# Sheet1.net
KiCad netlist of a schematic drawn in Altium Designer
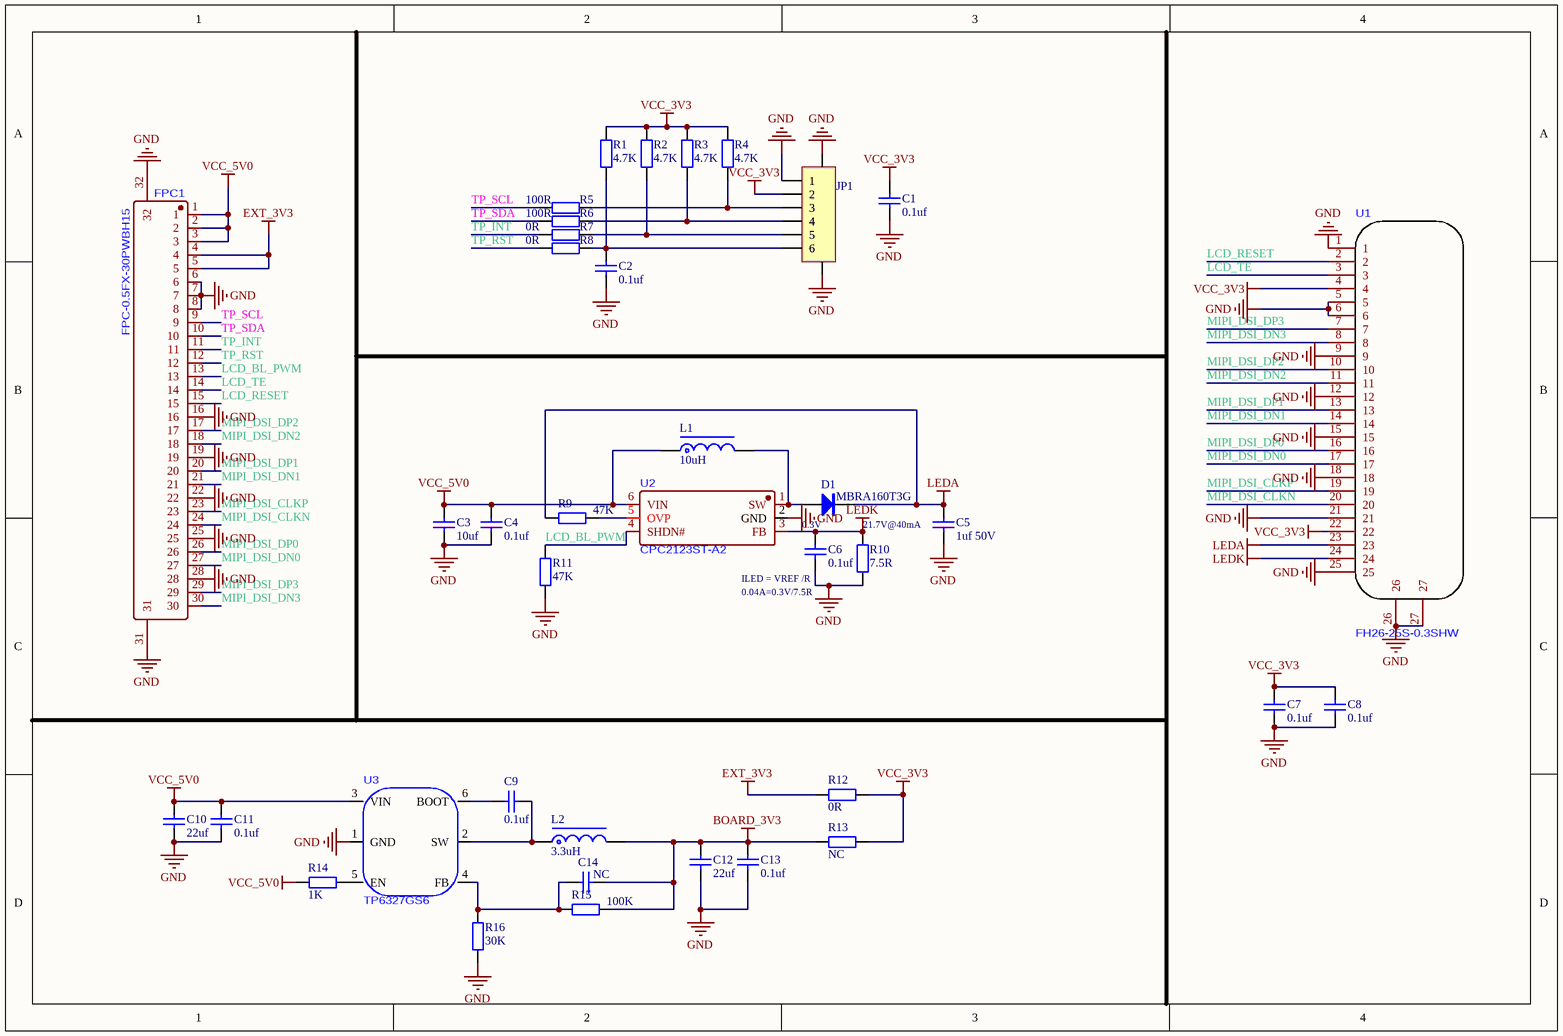
[diagram p0: Sheet1.SchDoc]

(export (version "E")
  (design (tool "Eeschema 10.0.6"))
  (components
    (comp (ref "C1")
      (value "0.1uf")
      (footprint "PCB1:C0402_L")
      (description "贴片电容/MLCC电容")
      (libsource (lib "5.5_MIPI_LCD") (part "C"))
    )
    (comp (ref "C2")
      (value "0.1uf")
      (footprint "PCB1:C0402_L")
      (description "贴片电容/MLCC电容")
      (libsource (lib "5.5_MIPI_LCD") (part "C"))
    )
    (comp (ref "C3")
      (value "10uf")
      (footprint "PCB1:C0402_L")
      (description "贴片电容/MLCC电容")
      (libsource (lib "5.5_MIPI_LCD") (part "C"))
    )
    (comp (ref "C4")
      (value "0.1uf")
      (footprint "PCB1:C0402_L")
      (description "贴片电容/MLCC电容")
      (libsource (lib "5.5_MIPI_LCD") (part "C"))
    )
    (comp (ref "C5")
      (value "1uf 50V")
      (footprint "PCB1:C0603_L")
      (description "贴片电容/MLCC电容")
      (libsource (lib "5.5_MIPI_LCD") (part "C"))
    )
    (comp (ref "C6")
      (value "0.1uf")
      (footprint "PCB1:C0402_L")
      (description "贴片电容/MLCC电容")
      (libsource (lib "5.5_MIPI_LCD") (part "C"))
    )
    (comp (ref "C7")
      (value "0.1uf")
      (footprint "PCB1:C0402_L")
      (description "贴片电容/MLCC电容")
      (libsource (lib "5.5_MIPI_LCD") (part "C"))
    )
    (comp (ref "C8")
      (value "0.1uf")
      (footprint "PCB1:C0402_L")
      (description "贴片电容/MLCC电容")
      (libsource (lib "5.5_MIPI_LCD") (part "C"))
    )
    (comp (ref "C9")
      (value "0.1uf")
      (footprint "PCB1:C0402_L")
      (description "贴片电容/MLCC电容")
      (libsource (lib "5.5_MIPI_LCD") (part "C"))
    )
    (comp (ref "C10")
      (value "22uf")
      (footprint "PCB1:C0603_L")
      (description "贴片电容/MLCC电容")
      (libsource (lib "5.5_MIPI_LCD") (part "C"))
    )
    (comp (ref "C11")
      (value "0.1uf")
      (footprint "PCB1:C0402_L")
      (description "贴片电容/MLCC电容")
      (libsource (lib "5.5_MIPI_LCD") (part "C"))
    )
    (comp (ref "C12")
      (value "22uf")
      (footprint "PCB1:C0603_L")
      (description "贴片电容/MLCC电容")
      (libsource (lib "5.5_MIPI_LCD") (part "C"))
    )
    (comp (ref "C13")
      (value "0.1uf")
      (footprint "PCB1:C0402_L")
      (description "贴片电容/MLCC电容")
      (libsource (lib "5.5_MIPI_LCD") (part "C"))
    )
    (comp (ref "C14")
      (value "NC")
      (footprint "PCB1:C0402_L")
      (description "贴片电容/MLCC电容")
      (libsource (lib "5.5_MIPI_LCD") (part "C"))
    )
    (comp (ref "D1")
      (value "MBRA160T3G")
      (footprint "PCB1:SMA")
      (description "整流二极管")
      (libsource (lib "5.5_MIPI_LCD") (part "M7"))
    )
    (comp (ref "FPC1")
      (value "FPC-0.5FX-30PWBH15")
      (footprint "PCB1:FPC-SMD_30P-P0.50_FPC-0.5FX-30PWBH15")
      (libsource (lib "5.5_MIPI_LCD") (part "FPC-0.5FX-30PWBH15"))
    )
    (comp (ref "JP1")
      (value "CON-6P")
      (footprint "PCB1:FPC0.5-WT-6P")
      (description "6P连接器")
      (libsource (lib "5.5_MIPI_LCD") (part "Header 6"))
    )
    (comp (ref "L1")
      (value "10uH")
      (footprint "PCB1:L-SMD-0420")
      (description "一体成型电感")
      (libsource (lib "5.5_MIPI_LCD") (part "L-Molding Choke"))
    )
    (comp (ref "L2")
      (value "3.3uH")
      (footprint "PCB1:L-SMD-0420")
      (description "一体成型电感")
      (libsource (lib "5.5_MIPI_LCD") (part "L-Molding Choke"))
    )
    (comp (ref "R1")
      (value "4.7K")
      (footprint "PCB1:R0402_L")
      (description "贴片电阻")
      (libsource (lib "5.5_MIPI_LCD") (part "R"))
    )
    (comp (ref "R2")
      (value "4.7K")
      (footprint "PCB1:R0402_L")
      (description "贴片电阻")
      (libsource (lib "5.5_MIPI_LCD") (part "R"))
    )
    (comp (ref "R3")
      (value "4.7K")
      (footprint "PCB1:R0402_L")
      (description "贴片电阻")
      (libsource (lib "5.5_MIPI_LCD") (part "R"))
    )
    (comp (ref "R4")
      (value "4.7K")
      (footprint "PCB1:R0402_L")
      (description "贴片电阻")
      (libsource (lib "5.5_MIPI_LCD") (part "R"))
    )
    (comp (ref "R5")
      (value "100R")
      (footprint "PCB1:R0402_L")
      (description "贴片电阻")
      (libsource (lib "5.5_MIPI_LCD") (part "R"))
    )
    (comp (ref "R6")
      (value "100R")
      (footprint "PCB1:R0402_L")
      (description "贴片电阻")
      (libsource (lib "5.5_MIPI_LCD") (part "R"))
    )
    (comp (ref "R7")
      (value "0R")
      (footprint "PCB1:R0402_L")
      (description "贴片电阻")
      (libsource (lib "5.5_MIPI_LCD") (part "R"))
    )
    (comp (ref "R8")
      (value "0R")
      (footprint "PCB1:R0402_L")
      (description "贴片电阻")
      (libsource (lib "5.5_MIPI_LCD") (part "R"))
    )
    (comp (ref "R9")
      (value "47K")
      (footprint "PCB1:R0402_L")
      (description "贴片电阻")
      (libsource (lib "5.5_MIPI_LCD") (part "R"))
    )
    (comp (ref "R10")
      (value "7.5R")
      (footprint "PCB1:R0603_L")
      (description "贴片电阻")
      (libsource (lib "5.5_MIPI_LCD") (part "R"))
    )
    (comp (ref "R11")
      (value "47K")
      (footprint "PCB1:R0402_L")
      (description "贴片电阻")
      (libsource (lib "5.5_MIPI_LCD") (part "R"))
    )
    (comp (ref "R12")
      (value "0R")
      (footprint "PCB1:R0603_L")
      (description "贴片电阻")
      (libsource (lib "5.5_MIPI_LCD") (part "R"))
    )
    (comp (ref "R13")
      (value "NC")
      (footprint "PCB1:R0603_L")
      (description "贴片电阻")
      (libsource (lib "5.5_MIPI_LCD") (part "R"))
    )
    (comp (ref "R14")
      (value "1K")
      (footprint "PCB1:R0402_L")
      (description "贴片电阻")
      (libsource (lib "5.5_MIPI_LCD") (part "R"))
    )
    (comp (ref "R15")
      (value "100K")
      (footprint "PCB1:R0402_L")
      (description "贴片电阻")
      (libsource (lib "5.5_MIPI_LCD") (part "R"))
    )
    (comp (ref "R16")
      (value "30K")
      (footprint "PCB1:R0402_L")
      (description "贴片电阻")
      (libsource (lib "5.5_MIPI_LCD") (part "R"))
    )
    (comp (ref "U1")
      (value "FH26-25S-0.3SHW")
      (footprint "PCB1:CONN-25PIN-FH26-25S-0.3SHW")
      (libsource (lib "5.5_MIPI_LCD") (part "FH26-25S-0.3SHW"))
    )
    (comp (ref "U2")
      (value "CPC2123ST-A2")
      (footprint "PCB1:SOT-23-6_L2.9-W1.6-P0.95-LS2.8-BR")
      (libsource (lib "5.5_MIPI_LCD") (part "CPC2123ST-A2"))
    )
    (comp (ref "U3")
      (value "TP6327GS6")
      (footprint "PCB1:SOT23_6")
      (libsource (lib "5.5_MIPI_LCD") (part "TP6327GS6"))
    )
  )
  (nets
    (net (code "1") (name "/LCD_BL_PWM") (class "Default")
      (node (ref "FPC1") (pin "13") (pinfunction "13_13") (pintype "passive"))
      (node (ref "R11") (pin "2") (pinfunction "2_2") (pintype "passive"))
      (node (ref "U2") (pin "4") (pinfunction "SHDN#_4") (pintype "passive"))
    )
    (net (code "2") (name "/LCD_RESET") (class "Default")
      (node (ref "FPC1") (pin "15") (pinfunction "15_15") (pintype "passive"))
      (node (ref "U1") (pin "2") (pinfunction "2_2") (pintype "passive"))
    )
    (net (code "3") (name "/LCD_TE") (class "Default")
      (node (ref "FPC1") (pin "14") (pinfunction "14_14") (pintype "passive"))
      (node (ref "U1") (pin "3") (pinfunction "3_3") (pintype "passive"))
    )
    (net (code "4") (name "/MIPI_DSI_CLKN") (class "Default")
      (node (ref "FPC1") (pin "24") (pinfunction "24_24") (pintype "passive"))
      (node (ref "U1") (pin "20") (pinfunction "20_20") (pintype "passive"))
    )
    (net (code "5") (name "/MIPI_DSI_CLKP") (class "Default")
      (node (ref "FPC1") (pin "23") (pinfunction "23_23") (pintype "passive"))
      (node (ref "U1") (pin "19") (pinfunction "19_19") (pintype "passive"))
    )
    (net (code "6") (name "/MIPI_DSI_DN0") (class "Default")
      (node (ref "FPC1") (pin "27") (pinfunction "27_27") (pintype "passive"))
      (node (ref "U1") (pin "17") (pinfunction "17_17") (pintype "passive"))
    )
    (net (code "7") (name "/MIPI_DSI_DN1") (class "Default")
      (node (ref "FPC1") (pin "21") (pinfunction "21_21") (pintype "passive"))
      (node (ref "U1") (pin "14") (pinfunction "14_14") (pintype "passive"))
    )
    (net (code "8") (name "/MIPI_DSI_DN2") (class "Default")
      (node (ref "FPC1") (pin "18") (pinfunction "18_18") (pintype "passive"))
      (node (ref "U1") (pin "11") (pinfunction "11_11") (pintype "passive"))
    )
    (net (code "9") (name "/MIPI_DSI_DN3") (class "Default")
      (node (ref "FPC1") (pin "30") (pinfunction "30_30") (pintype "passive"))
      (node (ref "U1") (pin "8") (pinfunction "8_8") (pintype "passive"))
    )
    (net (code "10") (name "/MIPI_DSI_DP0") (class "Default")
      (node (ref "FPC1") (pin "26") (pinfunction "26_26") (pintype "passive"))
      (node (ref "U1") (pin "16") (pinfunction "16_16") (pintype "passive"))
    )
    (net (code "11") (name "/MIPI_DSI_DP1") (class "Default")
      (node (ref "FPC1") (pin "20") (pinfunction "20_20") (pintype "passive"))
      (node (ref "U1") (pin "13") (pinfunction "13_13") (pintype "passive"))
    )
    (net (code "12") (name "/MIPI_DSI_DP2") (class "Default")
      (node (ref "FPC1") (pin "17") (pinfunction "17_17") (pintype "passive"))
      (node (ref "U1") (pin "10") (pinfunction "10_10") (pintype "passive"))
    )
    (net (code "13") (name "/MIPI_DSI_DP3") (class "Default")
      (node (ref "FPC1") (pin "29") (pinfunction "29_29") (pintype "passive"))
      (node (ref "U1") (pin "7") (pinfunction "7_7") (pintype "passive"))
    )
    (net (code "14") (name "/TP_INT") (class "Default")
      (node (ref "FPC1") (pin "11") (pinfunction "11_11") (pintype "passive"))
      (node (ref "R7") (pin "1") (pinfunction "1_1") (pintype "passive"))
    )
    (net (code "15") (name "/TP_RST") (class "Default")
      (node (ref "FPC1") (pin "12") (pinfunction "12_12") (pintype "passive"))
      (node (ref "R8") (pin "1") (pinfunction "1_1") (pintype "passive"))
    )
    (net (code "16") (name "/TP_SCL") (class "Default")
      (node (ref "FPC1") (pin "9") (pinfunction "9_9") (pintype "passive"))
      (node (ref "R5") (pin "1") (pinfunction "1_1") (pintype "passive"))
    )
    (net (code "17") (name "/TP_SDA") (class "Default")
      (node (ref "FPC1") (pin "10") (pinfunction "10_10") (pintype "passive"))
      (node (ref "R6") (pin "1") (pinfunction "1_1") (pintype "passive"))
    )
    (net (code "18") (name "BOARD_3V3") (class "Default")
      (node (ref "C12") (pin "2") (pinfunction "2_2") (pintype "passive"))
      (node (ref "C13") (pin "2") (pinfunction "2_2") (pintype "passive"))
      (node (ref "C14") (pin "1") (pinfunction "1_1") (pintype "passive"))
      (node (ref "L2") (pin "2") (pinfunction "2_2") (pintype "passive"))
      (node (ref "R13") (pin "1") (pinfunction "1_1") (pintype "passive"))
      (node (ref "R15") (pin "1") (pinfunction "1_1") (pintype "passive"))
    )
    (net (code "19") (name "EXT_3V3") (class "Default")
      (node (ref "FPC1") (pin "4") (pinfunction "4_4") (pintype "passive"))
      (node (ref "FPC1") (pin "5") (pinfunction "5_5") (pintype "passive"))
      (node (ref "R12") (pin "1") (pinfunction "1_1") (pintype "passive"))
    )
    (net (code "20") (name "GND") (class "Default")
      (node (ref "C1") (pin "1") (pinfunction "1_1") (pintype "passive"))
      (node (ref "C10") (pin "1") (pinfunction "1_1") (pintype "passive"))
      (node (ref "C11") (pin "1") (pinfunction "1_1") (pintype "passive"))
      (node (ref "C12") (pin "1") (pinfunction "1_1") (pintype "passive"))
      (node (ref "C13") (pin "1") (pinfunction "1_1") (pintype "passive"))
      (node (ref "C2") (pin "1") (pinfunction "1_1") (pintype "passive"))
      (node (ref "C3") (pin "1") (pinfunction "1_1") (pintype "passive"))
      (node (ref "C4") (pin "1") (pinfunction "1_1") (pintype "passive"))
      (node (ref "C5") (pin "1") (pinfunction "1_1") (pintype "passive"))
      (node (ref "C6") (pin "1") (pinfunction "1_1") (pintype "passive"))
      (node (ref "C7") (pin "1") (pinfunction "1_1") (pintype "passive"))
      (node (ref "C8") (pin "1") (pinfunction "1_1") (pintype "passive"))
      (node (ref "FPC1") (pin "16") (pinfunction "16_16") (pintype "passive"))
      (node (ref "FPC1") (pin "19") (pinfunction "19_19") (pintype "passive"))
      (node (ref "FPC1") (pin "22") (pinfunction "22_22") (pintype "passive"))
      (node (ref "FPC1") (pin "25") (pinfunction "25_25") (pintype "passive"))
      (node (ref "FPC1") (pin "28") (pinfunction "28_28") (pintype "passive"))
      (node (ref "FPC1") (pin "31") (pinfunction "31_31") (pintype "passive"))
      (node (ref "FPC1") (pin "32") (pinfunction "32_32") (pintype "passive"))
      (node (ref "FPC1") (pin "6") (pinfunction "6_6") (pintype "passive"))
      (node (ref "FPC1") (pin "7") (pinfunction "7_7") (pintype "passive"))
      (node (ref "FPC1") (pin "8") (pinfunction "8_8") (pintype "passive"))
      (node (ref "JP1") (pin "0") (pinfunction "0_0") (pintype "passive"))
      (node (ref "JP1") (pin "1") (pinfunction "1_1") (pintype "passive"))
      (node (ref "R10") (pin "1") (pinfunction "1_1") (pintype "passive"))
      (node (ref "R11") (pin "1") (pinfunction "1_1") (pintype "passive"))
      (node (ref "R16") (pin "2") (pinfunction "2_2") (pintype "passive"))
      (node (ref "U1") (pin "1") (pinfunction "1_1") (pintype "passive"))
      (node (ref "U1") (pin "12") (pinfunction "12_12") (pintype "passive"))
      (node (ref "U1") (pin "15") (pinfunction "15_15") (pintype "passive"))
      (node (ref "U1") (pin "18") (pinfunction "18_18") (pintype "passive"))
      (node (ref "U1") (pin "21") (pinfunction "21_21") (pintype "passive"))
      (node (ref "U1") (pin "25") (pinfunction "25_25") (pintype "passive"))
      (node (ref "U1") (pin "26") (pinfunction "26_26") (pintype "passive"))
      (node (ref "U1") (pin "27") (pinfunction "27_27") (pintype "passive"))
      (node (ref "U1") (pin "5") (pinfunction "5_5") (pintype "passive"))
      (node (ref "U1") (pin "6") (pinfunction "6_6") (pintype "passive"))
      (node (ref "U1") (pin "9") (pinfunction "9_9") (pintype "passive"))
      (node (ref "U2") (pin "2") (pinfunction "GND_2") (pintype "passive"))
      (node (ref "U3") (pin "1") (pinfunction "GND_1") (pintype "passive"))
    )
    (net (code "21") (name "LEDA") (class "Default")
      (node (ref "C5") (pin "2") (pinfunction "2_2") (pintype "passive"))
      (node (ref "D1") (pin "2") (pinfunction "K_2") (pintype "passive"))
      (node (ref "R9") (pin "2") (pinfunction "2_2") (pintype "passive"))
      (node (ref "U1") (pin "23") (pinfunction "23_23") (pintype "passive"))
    )
    (net (code "22") (name "LEDK") (class "Default")
      (node (ref "C6") (pin "2") (pinfunction "2_2") (pintype "passive"))
      (node (ref "R10") (pin "2") (pinfunction "2_2") (pintype "passive"))
      (node (ref "U1") (pin "24") (pinfunction "24_24") (pintype "passive"))
      (node (ref "U2") (pin "3") (pinfunction "FB_3") (pintype "passive"))
    )
    (net (code "23") (name "Net-(C2-Pad2)") (class "Default")
      (node (ref "C2") (pin "2") (pinfunction "2_2") (pintype "passive"))
      (node (ref "JP1") (pin "6") (pinfunction "6_6") (pintype "passive"))
      (node (ref "R1") (pin "1") (pinfunction "1_1") (pintype "passive"))
      (node (ref "R8") (pin "2") (pinfunction "2_2") (pintype "passive"))
    )
    (net (code "24") (name "Net-(D1-A)") (class "Default")
      (node (ref "D1") (pin "1") (pinfunction "A_1") (pintype "passive"))
      (node (ref "L1") (pin "2") (pinfunction "2_2") (pintype "passive"))
      (node (ref "U2") (pin "1") (pinfunction "SW_1") (pintype "passive"))
    )
    (net (code "25") (name "Net-(JP1-Pad3)") (class "Default")
      (node (ref "JP1") (pin "3") (pinfunction "3_3") (pintype "passive"))
      (node (ref "R4") (pin "1") (pinfunction "1_1") (pintype "passive"))
      (node (ref "R5") (pin "2") (pinfunction "2_2") (pintype "passive"))
    )
    (net (code "26") (name "Net-(JP1-Pad4)") (class "Default")
      (node (ref "JP1") (pin "4") (pinfunction "4_4") (pintype "passive"))
      (node (ref "R3") (pin "1") (pinfunction "1_1") (pintype "passive"))
      (node (ref "R6") (pin "2") (pinfunction "2_2") (pintype "passive"))
    )
    (net (code "27") (name "Net-(JP1-Pad5)") (class "Default")
      (node (ref "JP1") (pin "5") (pinfunction "5_5") (pintype "passive"))
      (node (ref "R2") (pin "1") (pinfunction "1_1") (pintype "passive"))
      (node (ref "R7") (pin "2") (pinfunction "2_2") (pintype "passive"))
    )
    (net (code "28") (name "Net-(U2-OVP)") (class "Default")
      (node (ref "R9") (pin "1") (pinfunction "1_1") (pintype "passive"))
      (node (ref "U2") (pin "5") (pinfunction "OVP_5") (pintype "passive"))
    )
    (net (code "29") (name "Net-(U3-BOOT)") (class "Default")
      (node (ref "C9") (pin "2") (pinfunction "2_2") (pintype "passive"))
      (node (ref "U3") (pin "6") (pinfunction "BOOT_6") (pintype "passive"))
    )
    (net (code "30") (name "Net-(U3-EN)") (class "Default")
      (node (ref "R14") (pin "1") (pinfunction "1_1") (pintype "passive"))
      (node (ref "U3") (pin "5") (pinfunction "EN_5") (pintype "passive"))
    )
    (net (code "31") (name "Net-(U3-FB)") (class "Default")
      (node (ref "C14") (pin "2") (pinfunction "2_2") (pintype "passive"))
      (node (ref "R15") (pin "2") (pinfunction "2_2") (pintype "passive"))
      (node (ref "R16") (pin "1") (pinfunction "1_1") (pintype "passive"))
      (node (ref "U3") (pin "4") (pinfunction "FB_4") (pintype "passive"))
    )
    (net (code "32") (name "Net-(U3-SW)") (class "Default")
      (node (ref "C9") (pin "1") (pinfunction "1_1") (pintype "passive"))
      (node (ref "L2") (pin "1") (pinfunction "1_1") (pintype "passive"))
      (node (ref "U3") (pin "2") (pinfunction "SW_2") (pintype "passive"))
    )
    (net (code "33") (name "VCC_3V3") (class "Default")
      (node (ref "C1") (pin "2") (pinfunction "2_2") (pintype "passive"))
      (node (ref "C7") (pin "2") (pinfunction "2_2") (pintype "passive"))
      (node (ref "C8") (pin "2") (pinfunction "2_2") (pintype "passive"))
      (node (ref "JP1") (pin "2") (pinfunction "2_2") (pintype "passive"))
      (node (ref "R1") (pin "2") (pinfunction "2_2") (pintype "passive"))
      (node (ref "R12") (pin "2") (pinfunction "2_2") (pintype "passive"))
      (node (ref "R13") (pin "2") (pinfunction "2_2") (pintype "passive"))
      (node (ref "R2") (pin "2") (pinfunction "2_2") (pintype "passive"))
      (node (ref "R3") (pin "2") (pinfunction "2_2") (pintype "passive"))
      (node (ref "R4") (pin "2") (pinfunction "2_2") (pintype "passive"))
      (node (ref "U1") (pin "22") (pinfunction "22_22") (pintype "passive"))
      (node (ref "U1") (pin "4") (pinfunction "4_4") (pintype "passive"))
    )
    (net (code "34") (name "VCC_5V0") (class "Default")
      (node (ref "C10") (pin "2") (pinfunction "2_2") (pintype "passive"))
      (node (ref "C11") (pin "2") (pinfunction "2_2") (pintype "passive"))
      (node (ref "C3") (pin "2") (pinfunction "2_2") (pintype "passive"))
      (node (ref "C4") (pin "2") (pinfunction "2_2") (pintype "passive"))
      (node (ref "FPC1") (pin "1") (pinfunction "1_1") (pintype "passive"))
      (node (ref "FPC1") (pin "2") (pinfunction "2_2") (pintype "passive"))
      (node (ref "FPC1") (pin "3") (pinfunction "3_3") (pintype "passive"))
      (node (ref "L1") (pin "1") (pinfunction "1_1") (pintype "passive"))
      (node (ref "R14") (pin "2") (pinfunction "2_2") (pintype "passive"))
      (node (ref "U2") (pin "6") (pinfunction "VIN_6") (pintype "passive"))
      (node (ref "U3") (pin "3") (pinfunction "VIN_3") (pintype "passive"))
    )
  )
)
